# SCHMETIC_ESP32_4LAYER.net
KiCad netlist of a schematic drawn in Altium Designer
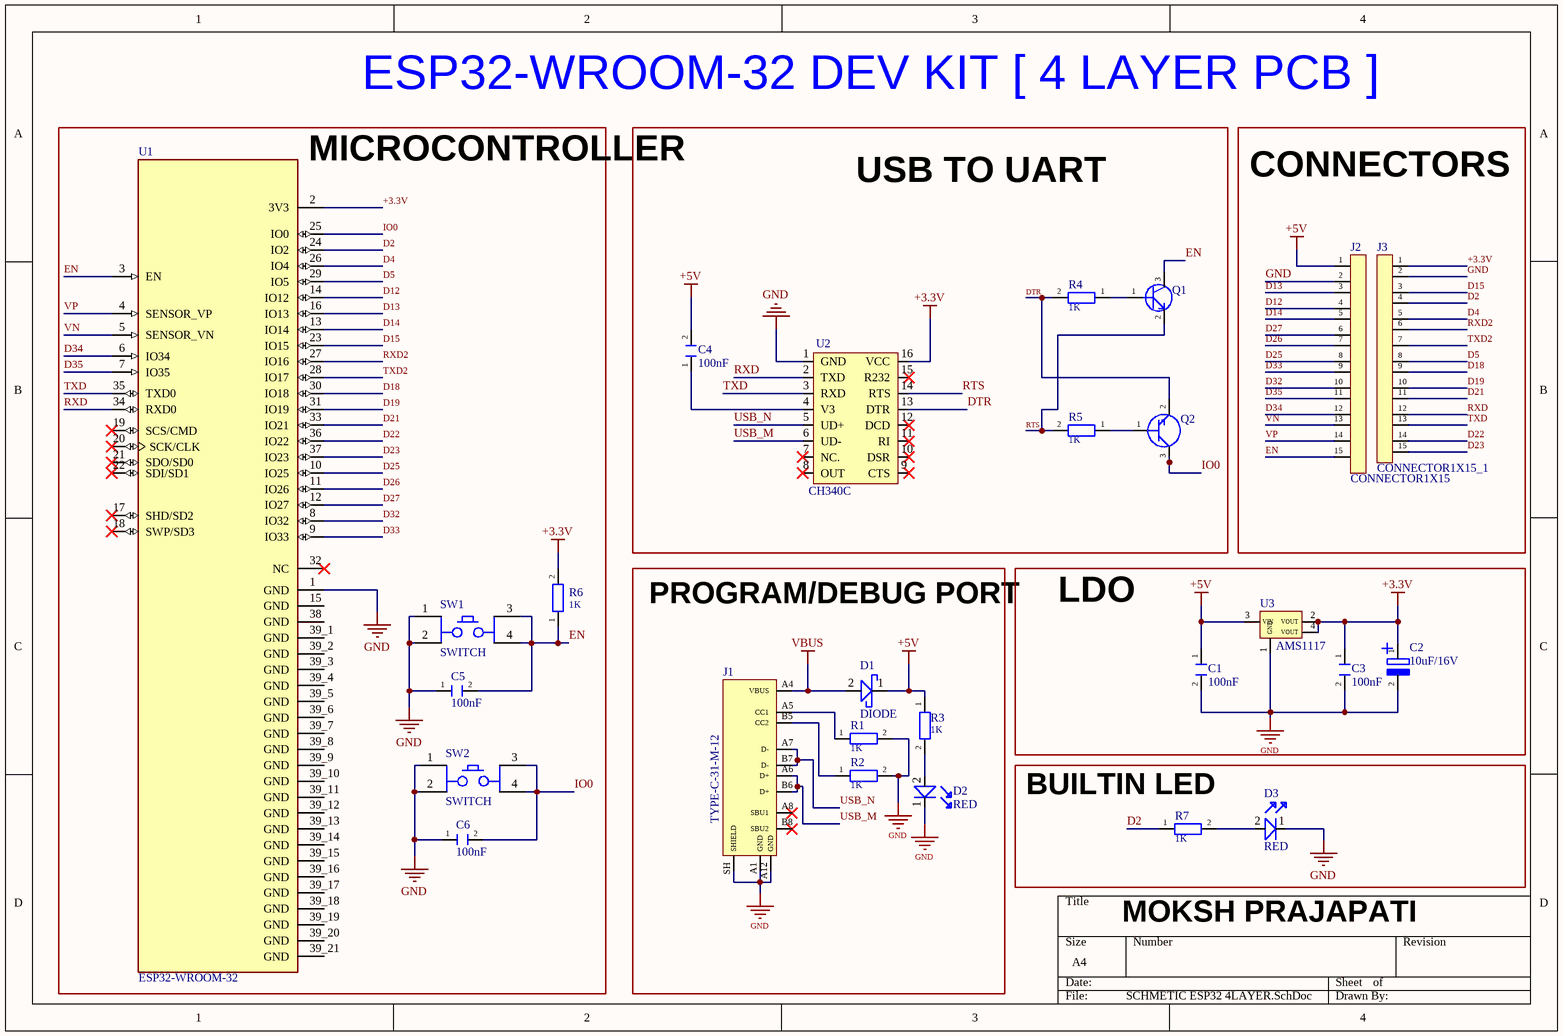
[diagram p0: SCHMETIC ESP32 4LAYER.SchDoc]

(export (version "E")
  (design (tool "Eeschema 10.0.6"))
  (components
    (comp (ref "C1")
      (value "100nF")
      (footprint "CAPACITOR0603-100nF")
      (description "UNPOLERIZED")
      (libsource (lib "PUSH BUTTON") (part "CAPACITOR.."))
    )
    (comp (ref "C2")
      (value "10uF/16V")
      (footprint "CAPACITOR0805-10uF")
      (libsource (lib "ESP32_WROOM_SCH_LIB.....") (part "TANTALUM CAPACITOR"))
    )
    (comp (ref "C3")
      (value "100nF")
      (footprint "CAPACITOR0603-100nF")
      (description "UNPOLERIZED")
      (libsource (lib "PUSH BUTTON") (part "CAPACITOR.."))
    )
    (comp (ref "C4")
      (value "100nF")
      (footprint "CAPACITOR0603-100nF")
      (description "UNPOLERIZED")
      (libsource (lib "PUSH BUTTON") (part "CAPACITOR.."))
    )
    (comp (ref "C5")
      (value "100nF")
      (footprint "CAPACITOR0603-100nF")
      (description "UNPOLERIZED")
      (libsource (lib "PUSH BUTTON") (part "CAPACITOR.."))
    )
    (comp (ref "C6")
      (value "100nF")
      (footprint "CAPACITOR0603-100nF")
      (description "UNPOLERIZED")
      (libsource (lib "PUSH BUTTON") (part "CAPACITOR.."))
    )
    (comp (ref "D1")
      (value "DIODE")
      (footprint "Schottky diode")
      (libsource (lib "PUSH BUTTON") (part "DIODE"))
    )
    (comp (ref "D2") (value "RED") (footprint "LED0603-RED") (libsource (lib "PUSH BUTTON") (part "LED")))
    (comp (ref "D3") (value "RED") (footprint "LED0603-RED") (libsource (lib "PUSH BUTTON") (part "LED")))
    (comp (ref "J1")
      (value "TYPE-C-31-M-12")
      (footprint "USB_TYPE_C")
      (libsource (lib "ESP32_WROOM_SCH_LIB.....") (part "USB TYPE C"))
    )
    (comp (ref "J2")
      (value "CONNECTOR1X15")
      (footprint "1X15 PIN HEADER")
      (libsource (lib "ESP32_WROOM_SCH_LIB.....") (part "CONNECTOR1X15"))
    )
    (comp (ref "J3")
      (value "CONNECTOR1X15_1")
      (footprint "1X15 PIN HEADER")
      (libsource (lib "ESP32_WROOM_SCH_LIB.....") (part "CONNECTOR1X15_1"))
    )
    (comp (ref "Q1")
      (value "MMBT3904LT1G")
      (footprint "NPN Transistor")
      (libsource (lib "ESP32_WROOM_SCH_LIB.....") (part "NPN TRANSISTOR"))
    )
    (comp (ref "Q2")
      (value "MMBT3904LT1G")
      (footprint "NPN Transistor")
      (libsource (lib "ESP32_WROOM_SCH_LIB.....") (part "NPN TRANSISTOR_1"))
    )
    (comp (ref "R1") (value "1K") (footprint "RESISTOR0603-1k") (libsource (lib "") (part "RES0805_1")))
    (comp (ref "R2") (value "1K") (footprint "RESISTOR0603-1k") (libsource (lib "") (part "RES0805_1")))
    (comp (ref "R3")
      (value "1K")
      (footprint "RESISTOR0603-1k")
      (libsource (lib "PUSH BUTTON") (part "RES0805"))
    )
    (comp (ref "R4") (value "1K") (footprint "RESISTOR0603-1k") (libsource (lib "") (part "RES0805_3")))
    (comp (ref "R5") (value "1K") (footprint "RESISTOR0603-1k") (libsource (lib "") (part "RES0805_3")))
    (comp (ref "R6") (value "1K") (footprint "RESISTOR0603-1k") (libsource (lib "") (part "RES0805_2")))
    (comp (ref "R7") (value "1K") (footprint "RESISTOR0603-1k") (libsource (lib "") (part "RES0805_1")))
    (comp (ref "SW1")
      (value "SWITCH")
      (footprint "PUSHBUTTON")
      (description "SWITCH PUSH SPST-NO 0.1A 32V")
      (libsource (lib "PUSH BUTTON") (part "SWITCH"))
    )
    (comp (ref "SW2")
      (value "SWITCH")
      (footprint "PUSHBUTTON")
      (description "SWITCH PUSH SPST-NO 0.1A 32V")
      (libsource (lib "PUSH BUTTON") (part "SWITCH"))
    )
    (comp (ref "U1")
      (value "ESP32-WROOM-32")
      (footprint "MODULE_ESP32-WROOM-32")
      (fields (field (name "MF") "Espressif Systems"))
      (libsource (lib "esp32_sch") (part "ESP32-WROOM-32"))
    )
    (comp (ref "U2")
      (value "CH340C")
      (footprint "CH340C")
      (libsource (lib "ESP32_WROOM_SCH_LIB.....") (part "CH340C"))
    )
    (comp (ref "U3")
      (value "AMS1117")
      (footprint "AMS1117-3.3")
      (libsource (lib "ESP32_WROOM_SCH_LIB.....") (part "AMS1117"))
    )
  )
  (nets
    (net (code "1") (name "+3.3V") (class "Default")
      (node (ref "C2") (pin "1") (pinfunction "+_1") (pintype "passive"))
      (node (ref "C3") (pin "1") (pintype "passive"))
      (node (ref "J3") (pin "1") (pintype "passive"))
      (node (ref "R6") (pin "2") (pintype "passive"))
      (node (ref "U1") (pin "2") (pinfunction "3V3_2") (pintype "power_in"))
      (node (ref "U2") (pin "16") (pinfunction "VCC_16") (pintype "passive"))
      (node (ref "U3") (pin "2") (pinfunction "VOUT_2") (pintype "passive"))
      (node (ref "U3") (pin "4") (pinfunction "VOUT_4") (pintype "passive"))
    )
    (net (code "2") (name "+5V") (class "Default")
      (node (ref "C1") (pin "1") (pintype "passive"))
      (node (ref "C4") (pin "2") (pintype "passive"))
      (node (ref "D1") (pin "1") (pinfunction "-_1") (pintype "passive"))
      (node (ref "J2") (pin "1") (pintype "passive"))
      (node (ref "R3") (pin "1") (pintype "passive"))
      (node (ref "U3") (pin "3") (pinfunction "VIN_3") (pintype "passive"))
    )
    (net (code "3") (name "/D2") (class "Default")
      (node (ref "J3") (pin "4") (pintype "passive"))
      (node (ref "R7") (pin "1") (pintype "passive"))
      (node (ref "U1") (pin "24") (pinfunction "IO2_24") (pintype "bidirectional"))
    )
    (net (code "4") (name "/D4") (class "Default")
      (node (ref "J3") (pin "5") (pintype "passive"))
      (node (ref "U1") (pin "26") (pinfunction "IO4_26") (pintype "bidirectional"))
    )
    (net (code "5") (name "/D5") (class "Default")
      (node (ref "J3") (pin "8") (pintype "passive"))
      (node (ref "U1") (pin "29") (pinfunction "IO5_29") (pintype "bidirectional"))
    )
    (net (code "6") (name "/D12") (class "Default")
      (node (ref "J2") (pin "4") (pintype "passive"))
      (node (ref "U1") (pin "14") (pinfunction "IO12_14") (pintype "bidirectional"))
    )
    (net (code "7") (name "/D13") (class "Default")
      (node (ref "J2") (pin "3") (pintype "passive"))
      (node (ref "U1") (pin "16") (pinfunction "IO13_16") (pintype "bidirectional"))
    )
    (net (code "8") (name "/D14") (class "Default")
      (node (ref "J2") (pin "5") (pintype "passive"))
      (node (ref "U1") (pin "13") (pinfunction "IO14_13") (pintype "bidirectional"))
    )
    (net (code "9") (name "/D15") (class "Default")
      (node (ref "J3") (pin "3") (pintype "passive"))
      (node (ref "U1") (pin "23") (pinfunction "IO15_23") (pintype "bidirectional"))
    )
    (net (code "10") (name "/D18") (class "Default")
      (node (ref "J3") (pin "9") (pintype "passive"))
      (node (ref "U1") (pin "30") (pinfunction "IO18_30") (pintype "bidirectional"))
    )
    (net (code "11") (name "/D19") (class "Default")
      (node (ref "J3") (pin "10") (pintype "passive"))
      (node (ref "U1") (pin "31") (pinfunction "IO19_31") (pintype "bidirectional"))
    )
    (net (code "12") (name "/D21") (class "Default")
      (node (ref "J3") (pin "11") (pintype "passive"))
      (node (ref "U1") (pin "33") (pinfunction "IO21_33") (pintype "bidirectional"))
    )
    (net (code "13") (name "/D22") (class "Default")
      (node (ref "J3") (pin "14") (pintype "passive"))
      (node (ref "U1") (pin "36") (pinfunction "IO22_36") (pintype "bidirectional"))
    )
    (net (code "14") (name "/D23") (class "Default")
      (node (ref "J3") (pin "15") (pintype "passive"))
      (node (ref "U1") (pin "37") (pinfunction "IO23_37") (pintype "bidirectional"))
    )
    (net (code "15") (name "/D25") (class "Default")
      (node (ref "J2") (pin "8") (pintype "passive"))
      (node (ref "U1") (pin "10") (pinfunction "IO25_10") (pintype "bidirectional"))
    )
    (net (code "16") (name "/D26") (class "Default")
      (node (ref "J2") (pin "7") (pintype "passive"))
      (node (ref "U1") (pin "11") (pinfunction "IO26_11") (pintype "bidirectional"))
    )
    (net (code "17") (name "/D27") (class "Default")
      (node (ref "J2") (pin "6") (pintype "passive"))
      (node (ref "U1") (pin "12") (pinfunction "IO27_12") (pintype "bidirectional"))
    )
    (net (code "18") (name "/D32") (class "Default")
      (node (ref "J2") (pin "10") (pintype "passive"))
      (node (ref "U1") (pin "8") (pinfunction "IO32_8") (pintype "bidirectional"))
    )
    (net (code "19") (name "/D33") (class "Default")
      (node (ref "J2") (pin "9") (pintype "passive"))
      (node (ref "U1") (pin "9") (pinfunction "IO33_9") (pintype "bidirectional"))
    )
    (net (code "20") (name "/D34") (class "Default")
      (node (ref "J2") (pin "12") (pintype "passive"))
      (node (ref "U1") (pin "6") (pinfunction "IO34_6") (pintype "input"))
    )
    (net (code "21") (name "/D35") (class "Default")
      (node (ref "J2") (pin "11") (pintype "passive"))
      (node (ref "U1") (pin "7") (pinfunction "IO35_7") (pintype "input"))
    )
    (net (code "22") (name "/DTR") (class "Default")
      (node (ref "Q2") (pin "2") (pinfunction "B_2") (pintype "passive"))
      (node (ref "R4") (pin "2") (pintype "passive"))
      (node (ref "U2") (pin "13") (pinfunction "DTR_13") (pintype "passive"))
    )
    (net (code "23") (name "/EN") (class "Default")
      (node (ref "C5") (pin "2") (pintype "passive"))
      (node (ref "J2") (pin "15") (pintype "passive"))
      (node (ref "Q1") (pin "3") (pinfunction "B_3") (pintype "passive"))
      (node (ref "R6") (pin "1") (pintype "passive"))
      (node (ref "SW1") (pin "3") (pinfunction "3_3") (pintype "passive"))
      (node (ref "SW1") (pin "4") (pinfunction "4_4") (pintype "passive"))
      (node (ref "U1") (pin "3") (pinfunction "EN_3") (pintype "input"))
    )
    (net (code "24") (name "/IO0") (class "Default")
      (node (ref "C6") (pin "2") (pintype "passive"))
      (node (ref "Q2") (pin "3") (pinfunction "B_3") (pintype "passive"))
      (node (ref "SW2") (pin "3") (pinfunction "3_3") (pintype "passive"))
      (node (ref "SW2") (pin "4") (pinfunction "4_4") (pintype "passive"))
      (node (ref "U1") (pin "25") (pinfunction "IO0_25") (pintype "bidirectional"))
    )
    (net (code "25") (name "/RTS") (class "Default")
      (node (ref "Q1") (pin "2") (pinfunction "B_2") (pintype "passive"))
      (node (ref "R5") (pin "2") (pintype "passive"))
      (node (ref "U2") (pin "14") (pinfunction "RTS_14") (pintype "passive"))
    )
    (net (code "26") (name "/RXD") (class "Default")
      (node (ref "J3") (pin "12") (pintype "passive"))
      (node (ref "U1") (pin "34") (pinfunction "RXD0_34") (pintype "bidirectional"))
      (node (ref "U2") (pin "2") (pinfunction "TXD_2") (pintype "passive"))
    )
    (net (code "27") (name "/RXD2") (class "Default")
      (node (ref "J3") (pin "6") (pintype "passive"))
      (node (ref "U1") (pin "27") (pinfunction "IO16_27") (pintype "bidirectional"))
    )
    (net (code "28") (name "/TXD") (class "Default")
      (node (ref "J3") (pin "13") (pintype "passive"))
      (node (ref "U1") (pin "35") (pinfunction "TXD0_35") (pintype "bidirectional"))
      (node (ref "U2") (pin "3") (pinfunction "RXD_3") (pintype "passive"))
    )
    (net (code "29") (name "/TXD2") (class "Default")
      (node (ref "J3") (pin "7") (pintype "passive"))
      (node (ref "U1") (pin "28") (pinfunction "IO17_28") (pintype "bidirectional"))
    )
    (net (code "30") (name "/USB_M") (class "Default")
      (node (ref "J1") (pin "A6") (pinfunction "D+_A6") (pintype "passive"))
      (node (ref "J1") (pin "B6") (pinfunction "D+_B6") (pintype "passive"))
      (node (ref "U2") (pin "6") (pinfunction "UD-_6") (pintype "passive"))
    )
    (net (code "31") (name "/USB_N") (class "Default")
      (node (ref "J1") (pin "A7") (pinfunction "D-_A7") (pintype "passive"))
      (node (ref "J1") (pin "B7") (pinfunction "D-_B7") (pintype "passive"))
      (node (ref "U2") (pin "5") (pinfunction "UD+_5") (pintype "passive"))
    )
    (net (code "32") (name "/VN") (class "Default")
      (node (ref "J2") (pin "13") (pintype "passive"))
      (node (ref "U1") (pin "5") (pinfunction "SENSOR_VN_5") (pintype "input"))
    )
    (net (code "33") (name "/VP") (class "Default")
      (node (ref "J2") (pin "14") (pintype "passive"))
      (node (ref "U1") (pin "4") (pinfunction "SENSOR_VP_4") (pintype "input"))
    )
    (net (code "34") (name "GND") (class "Default")
      (node (ref "C1") (pin "2") (pintype "passive"))
      (node (ref "C2") (pin "2") (pinfunction "-_2") (pintype "passive"))
      (node (ref "C3") (pin "2") (pintype "passive"))
      (node (ref "C5") (pin "1") (pintype "passive"))
      (node (ref "C6") (pin "1") (pintype "passive"))
      (node (ref "D2") (pin "1") (pinfunction "-_1") (pintype "passive"))
      (node (ref "D3") (pin "1") (pinfunction "-_1") (pintype "passive"))
      (node (ref "J1") (pin "A1") (pinfunction "GND_A1") (pintype "passive"))
      (node (ref "J1") (pin "A12") (pinfunction "GND_A12") (pintype "passive"))
      (node (ref "J1") (pin "SH") (pinfunction "SHIELD_SH") (pintype "passive"))
      (node (ref "J2") (pin "2") (pintype "passive"))
      (node (ref "J3") (pin "2") (pintype "passive"))
      (node (ref "R1") (pin "2") (pintype "passive"))
      (node (ref "R2") (pin "2") (pintype "passive"))
      (node (ref "SW1") (pin "1") (pinfunction "1_1") (pintype "passive"))
      (node (ref "SW1") (pin "2") (pinfunction "2_2") (pintype "passive"))
      (node (ref "SW2") (pin "1") (pinfunction "1_1") (pintype "passive"))
      (node (ref "SW2") (pin "2") (pinfunction "2_2") (pintype "passive"))
      (node (ref "U1") (pin "1") (pinfunction "GND_1") (pintype "power_in"))
      (node (ref "U2") (pin "1") (pinfunction "GND_1") (pintype "passive"))
      (node (ref "U3") (pin "1") (pinfunction "GND_1") (pintype "passive"))
    )
    (net (code "35") (name "Net-(D2-+)") (class "Default")
      (node (ref "D2") (pin "2") (pinfunction "+_2") (pintype "passive"))
      (node (ref "R3") (pin "2") (pintype "passive"))
    )
    (net (code "36") (name "Net-(D3-+)") (class "Default")
      (node (ref "D3") (pin "2") (pinfunction "+_2") (pintype "passive"))
      (node (ref "R7") (pin "2") (pintype "passive"))
    )
    (net (code "37") (name "Net-(J1-CC1)") (class "Default")
      (node (ref "J1") (pin "A5") (pinfunction "CC1_A5") (pintype "passive"))
      (node (ref "R1") (pin "1") (pintype "passive"))
    )
    (net (code "38") (name "Net-(J1-CC2)") (class "Default")
      (node (ref "J1") (pin "B5") (pinfunction "CC2_B5") (pintype "passive"))
      (node (ref "R2") (pin "1") (pintype "passive"))
    )
    (net (code "39") (name "Net-(Q1-B-Pad1)") (class "Default")
      (node (ref "Q1") (pin "1") (pinfunction "B_1") (pintype "passive"))
      (node (ref "R4") (pin "1") (pintype "passive"))
    )
    (net (code "40") (name "Net-(Q2-B-Pad1)") (class "Default")
      (node (ref "Q2") (pin "1") (pinfunction "B_1") (pintype "passive"))
      (node (ref "R5") (pin "1") (pintype "passive"))
    )
    (net (code "41") (name "Net-(U2-V3)") (class "Default")
      (node (ref "C4") (pin "1") (pintype "passive"))
      (node (ref "U2") (pin "4") (pinfunction "V3_4") (pintype "passive"))
    )
    (net (code "42") (name "VBUS") (class "Default")
      (node (ref "D1") (pin "2") (pinfunction "+_2") (pintype "passive"))
      (node (ref "J1") (pin "A4") (pinfunction "VBUS_A4") (pintype "passive"))
    )
    (net (code "43") (name "unconnected-(J1-SBU1-PadA8)") (class "Default")
      (node (ref "J1") (pin "A8") (pinfunction "SBU1_A8") (pintype "passive+no_connect"))
    )
    (net (code "44") (name "unconnected-(J1-SBU2-PadB8)") (class "Default")
      (node (ref "J1") (pin "B8") (pinfunction "SBU2_B8") (pintype "passive+no_connect"))
    )
    (net (code "45") (name "unconnected-(U1-GND-Pad15)") (class "Default")
      (node (ref "U1") (pin "15") (pinfunction "GND_15") (pintype "power_in"))
    )
    (net (code "46") (name "unconnected-(U1-GND-Pad38)") (class "Default")
      (node (ref "U1") (pin "38") (pinfunction "GND_38") (pintype "power_in"))
    )
    (net (code "47") (name "unconnected-(U1-GND-Pad39_1)") (class "Default")
      (node (ref "U1") (pin "39_1") (pinfunction "GND_39_1") (pintype "power_in"))
    )
    (net (code "48") (name "unconnected-(U1-GND-Pad39_2)") (class "Default")
      (node (ref "U1") (pin "39_2") (pinfunction "GND_39_2") (pintype "power_in"))
    )
    (net (code "49") (name "unconnected-(U1-GND-Pad39_3)") (class "Default")
      (node (ref "U1") (pin "39_3") (pinfunction "GND_39_3") (pintype "power_in"))
    )
    (net (code "50") (name "unconnected-(U1-GND-Pad39_4)") (class "Default")
      (node (ref "U1") (pin "39_4") (pinfunction "GND_39_4") (pintype "power_in"))
    )
    (net (code "51") (name "unconnected-(U1-GND-Pad39_5)") (class "Default")
      (node (ref "U1") (pin "39_5") (pinfunction "GND_39_5") (pintype "power_in"))
    )
    (net (code "52") (name "unconnected-(U1-GND-Pad39_6)") (class "Default")
      (node (ref "U1") (pin "39_6") (pinfunction "GND_39_6") (pintype "power_in"))
    )
    (net (code "53") (name "unconnected-(U1-GND-Pad39_7)") (class "Default")
      (node (ref "U1") (pin "39_7") (pinfunction "GND_39_7") (pintype "power_in"))
    )
    (net (code "54") (name "unconnected-(U1-GND-Pad39_8)") (class "Default")
      (node (ref "U1") (pin "39_8") (pinfunction "GND_39_8") (pintype "power_in"))
    )
    (net (code "55") (name "unconnected-(U1-GND-Pad39_9)") (class "Default")
      (node (ref "U1") (pin "39_9") (pinfunction "GND_39_9") (pintype "power_in"))
    )
    (net (code "56") (name "unconnected-(U1-GND-Pad39_10)") (class "Default")
      (node (ref "U1") (pin "39_10") (pinfunction "GND_39_10") (pintype "power_in"))
    )
    (net (code "57") (name "unconnected-(U1-GND-Pad39_11)") (class "Default")
      (node (ref "U1") (pin "39_11") (pinfunction "GND_39_11") (pintype "power_in"))
    )
    (net (code "58") (name "unconnected-(U1-GND-Pad39_12)") (class "Default")
      (node (ref "U1") (pin "39_12") (pinfunction "GND_39_12") (pintype "power_in"))
    )
    (net (code "59") (name "unconnected-(U1-GND-Pad39_13)") (class "Default")
      (node (ref "U1") (pin "39_13") (pinfunction "GND_39_13") (pintype "power_in"))
    )
    (net (code "60") (name "unconnected-(U1-GND-Pad39_14)") (class "Default")
      (node (ref "U1") (pin "39_14") (pinfunction "GND_39_14") (pintype "power_in"))
    )
    (net (code "61") (name "unconnected-(U1-GND-Pad39_15)") (class "Default")
      (node (ref "U1") (pin "39_15") (pinfunction "GND_39_15") (pintype "power_in"))
    )
    (net (code "62") (name "unconnected-(U1-GND-Pad39_16)") (class "Default")
      (node (ref "U1") (pin "39_16") (pinfunction "GND_39_16") (pintype "power_in"))
    )
    (net (code "63") (name "unconnected-(U1-GND-Pad39_17)") (class "Default")
      (node (ref "U1") (pin "39_17") (pinfunction "GND_39_17") (pintype "power_in"))
    )
    (net (code "64") (name "unconnected-(U1-GND-Pad39_18)") (class "Default")
      (node (ref "U1") (pin "39_18") (pinfunction "GND_39_18") (pintype "power_in"))
    )
    (net (code "65") (name "unconnected-(U1-GND-Pad39_19)") (class "Default")
      (node (ref "U1") (pin "39_19") (pinfunction "GND_39_19") (pintype "power_in"))
    )
    (net (code "66") (name "unconnected-(U1-GND-Pad39_20)") (class "Default")
      (node (ref "U1") (pin "39_20") (pinfunction "GND_39_20") (pintype "power_in"))
    )
    (net (code "67") (name "unconnected-(U1-GND-Pad39_21)") (class "Default")
      (node (ref "U1") (pin "39_21") (pinfunction "GND_39_21") (pintype "power_in"))
    )
    (net (code "68") (name "unconnected-(U1-NC-Pad32)") (class "Default")
      (node (ref "U1") (pin "32") (pinfunction "NC_32") (pintype "passive+no_connect"))
    )
    (net (code "69") (name "unconnected-(U1-SCK{slash}CLK-Pad20)") (class "Default")
      (node (ref "U1") (pin "20") (pinfunction "SCK/CLK_20") (pintype "bidirectional+no_connect"))
    )
    (net (code "70") (name "unconnected-(U1-SCS{slash}CMD-Pad19)") (class "Default")
      (node (ref "U1") (pin "19") (pinfunction "SCS/CMD_19") (pintype "bidirectional+no_connect"))
    )
    (net (code "71") (name "unconnected-(U1-SDI{slash}SD1-Pad22)") (class "Default")
      (node (ref "U1") (pin "22") (pinfunction "SDI/SD1_22") (pintype "bidirectional+no_connect"))
    )
    (net (code "72") (name "unconnected-(U1-SDO{slash}SD0-Pad21)") (class "Default")
      (node (ref "U1") (pin "21") (pinfunction "SDO/SD0_21") (pintype "bidirectional+no_connect"))
    )
    (net (code "73") (name "unconnected-(U1-SHD{slash}SD2-Pad17)") (class "Default")
      (node (ref "U1") (pin "17") (pinfunction "SHD/SD2_17") (pintype "bidirectional+no_connect"))
    )
    (net (code "74") (name "unconnected-(U1-SWP{slash}SD3-Pad18)") (class "Default")
      (node (ref "U1") (pin "18") (pinfunction "SWP/SD3_18") (pintype "bidirectional+no_connect"))
    )
    (net (code "75") (name "unconnected-(U2-CTS-Pad9)") (class "Default")
      (node (ref "U2") (pin "9") (pinfunction "CTS_9") (pintype "passive+no_connect"))
    )
    (net (code "76") (name "unconnected-(U2-DCD-Pad12)") (class "Default")
      (node (ref "U2") (pin "12") (pinfunction "DCD_12") (pintype "passive+no_connect"))
    )
    (net (code "77") (name "unconnected-(U2-DSR-Pad10)") (class "Default")
      (node (ref "U2") (pin "10") (pinfunction "DSR_10") (pintype "passive+no_connect"))
    )
    (net (code "78") (name "unconnected-(U2-NC.-Pad7)") (class "Default")
      (node (ref "U2") (pin "7") (pinfunction "NC._7") (pintype "passive+no_connect"))
    )
    (net (code "79") (name "unconnected-(U2-OUT-Pad8)") (class "Default")
      (node (ref "U2") (pin "8") (pinfunction "OUT_8") (pintype "passive+no_connect"))
    )
    (net (code "80") (name "unconnected-(U2-R232-Pad15)") (class "Default")
      (node (ref "U2") (pin "15") (pinfunction "R232_15") (pintype "passive+no_connect"))
    )
    (net (code "81") (name "unconnected-(U2-RI-Pad11)") (class "Default")
      (node (ref "U2") (pin "11") (pinfunction "RI_11") (pintype "passive+no_connect"))
    )
  )
)
